# DSP.net
KiCad netlist of a schematic drawn in Altium Designer
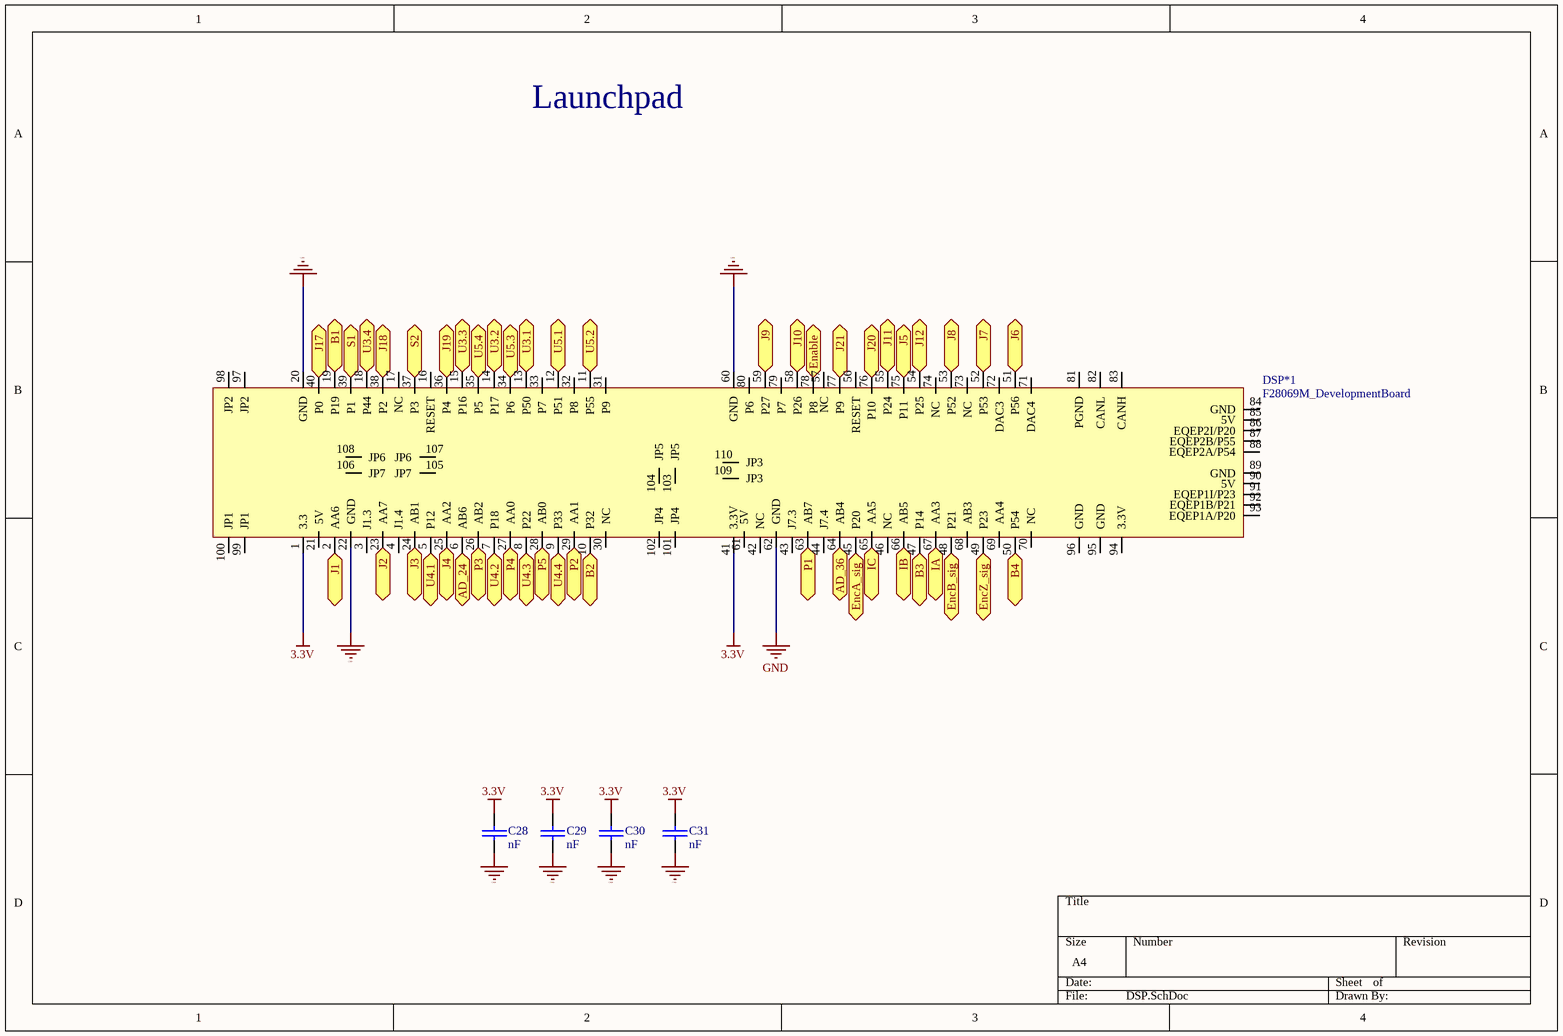
[diagram p0: DSP.SchDoc]

(export (version "E")
  (design (tool "Eeschema 10.0.6"))
  (components
    (comp (ref "C28")
      (value "nF")
      (footprint "1206")
      (description "Condensador")
      (libsource (lib "SCH_Lib") (part "Condensador"))
    )
    (comp (ref "C29")
      (value "nF")
      (footprint "1206")
      (description "Condensador")
      (libsource (lib "SCH_Lib") (part "Condensador"))
    )
    (comp (ref "C30")
      (value "nF")
      (footprint "1206")
      (description "Condensador")
      (libsource (lib "SCH_Lib") (part "Condensador"))
    )
    (comp (ref "C31")
      (value "nF")
      (footprint "1206")
      (description "Condensador")
      (libsource (lib "SCH_Lib") (part "Condensador"))
    )
    (comp (ref "DSP*1")
      (value "F28069M_DevelopmentBoard")
      (footprint "F28069M_DevelopmentBoardDOWN")
      (libsource (lib "DSP") (part "F28069M_DevelopmentBoard"))
    )
  )
  (nets
    (net (code "1") (name "/AD_24") (class "Default")
      (node (ref "DSP*1") (pin "6") (pinfunction "AB6_6") (pintype "passive"))
    )
    (net (code "2") (name "/AD_36") (class "Default")
      (node (ref "DSP*1") (pin "64") (pinfunction "AB4_64") (pintype "passive"))
    )
    (net (code "3") (name "/B1") (class "Default")
      (node (ref "DSP*1") (pin "19") (pinfunction "P19_19") (pintype "passive"))
    )
    (net (code "4") (name "/B2") (class "Default")
      (node (ref "DSP*1") (pin "10") (pinfunction "P32_10") (pintype "passive"))
    )
    (net (code "5") (name "/B3") (class "Default")
      (node (ref "DSP*1") (pin "47") (pinfunction "P14_47") (pintype "passive"))
    )
    (net (code "6") (name "/B4") (class "Default")
      (node (ref "DSP*1") (pin "50") (pinfunction "P54_50") (pintype "passive"))
    )
    (net (code "7") (name "/Enable") (class "Default")
      (node (ref "DSP*1") (pin "78") (pinfunction "P8_78") (pintype "passive"))
    )
    (net (code "8") (name "/EncA_sig") (class "Default")
      (node (ref "DSP*1") (pin "45") (pinfunction "P20_45") (pintype "passive"))
    )
    (net (code "9") (name "/EncB_sig") (class "Default")
      (node (ref "DSP*1") (pin "48") (pinfunction "P21_48") (pintype "passive"))
    )
    (net (code "10") (name "/EncZ_sig") (class "Default")
      (node (ref "DSP*1") (pin "49") (pinfunction "P23_49") (pintype "passive"))
    )
    (net (code "11") (name "/IA") (class "Default")
      (node (ref "DSP*1") (pin "67") (pinfunction "AA3_67") (pintype "passive"))
    )
    (net (code "12") (name "/IB") (class "Default")
      (node (ref "DSP*1") (pin "66") (pinfunction "AB5_66") (pintype "passive"))
    )
    (net (code "13") (name "/IC") (class "Default")
      (node (ref "DSP*1") (pin "65") (pinfunction "AA5_65") (pintype "passive"))
    )
    (net (code "14") (name "/J1") (class "Default")
      (node (ref "DSP*1") (pin "2") (pinfunction "AA6_2") (pintype "passive"))
    )
    (net (code "15") (name "/J2") (class "Default")
      (node (ref "DSP*1") (pin "23") (pinfunction "AA7_23") (pintype "passive"))
    )
    (net (code "16") (name "/J3") (class "Default")
      (node (ref "DSP*1") (pin "24") (pinfunction "AB1_24") (pintype "passive"))
    )
    (net (code "17") (name "/J4") (class "Default")
      (node (ref "DSP*1") (pin "25") (pinfunction "AA2_25") (pintype "passive"))
    )
    (net (code "18") (name "/J5") (class "Default")
      (node (ref "DSP*1") (pin "75") (pinfunction "P11_75") (pintype "passive"))
    )
    (net (code "19") (name "/J6") (class "Default")
      (node (ref "DSP*1") (pin "51") (pinfunction "P56_51") (pintype "passive"))
    )
    (net (code "20") (name "/J7") (class "Default")
      (node (ref "DSP*1") (pin "52") (pinfunction "P53_52") (pintype "passive"))
    )
    (net (code "21") (name "/J8") (class "Default")
      (node (ref "DSP*1") (pin "53") (pinfunction "P52_53") (pintype "passive"))
    )
    (net (code "22") (name "/J9") (class "Default")
      (node (ref "DSP*1") (pin "59") (pinfunction "P27_59") (pintype "passive"))
    )
    (net (code "23") (name "/J10") (class "Default")
      (node (ref "DSP*1") (pin "58") (pinfunction "P26_58") (pintype "passive"))
    )
    (net (code "24") (name "/J11") (class "Default")
      (node (ref "DSP*1") (pin "55") (pinfunction "P24_55") (pintype "passive"))
    )
    (net (code "25") (name "/J12") (class "Default")
      (node (ref "DSP*1") (pin "54") (pinfunction "P25_54") (pintype "passive"))
    )
    (net (code "26") (name "/J17") (class "Default")
      (node (ref "DSP*1") (pin "40") (pinfunction "P0_40") (pintype "passive"))
    )
    (net (code "27") (name "/J18") (class "Default")
      (node (ref "DSP*1") (pin "38") (pinfunction "P2_38") (pintype "passive"))
    )
    (net (code "28") (name "/J19") (class "Default")
      (node (ref "DSP*1") (pin "36") (pinfunction "P4_36") (pintype "passive"))
    )
    (net (code "29") (name "/J20") (class "Default")
      (node (ref "DSP*1") (pin "76") (pinfunction "P10_76") (pintype "passive"))
    )
    (net (code "30") (name "/J21") (class "Default")
      (node (ref "DSP*1") (pin "77") (pinfunction "P9_77") (pintype "passive"))
    )
    (net (code "31") (name "/P1") (class "Default")
      (node (ref "DSP*1") (pin "63") (pinfunction "AB7_63") (pintype "passive"))
    )
    (net (code "32") (name "/P2") (class "Default")
      (node (ref "DSP*1") (pin "29") (pinfunction "AA1_29") (pintype "passive"))
    )
    (net (code "33") (name "/P3") (class "Default")
      (node (ref "DSP*1") (pin "26") (pinfunction "AB2_26") (pintype "passive"))
    )
    (net (code "34") (name "/P4") (class "Default")
      (node (ref "DSP*1") (pin "27") (pinfunction "AA0_27") (pintype "passive"))
    )
    (net (code "35") (name "/P5") (class "Default")
      (node (ref "DSP*1") (pin "28") (pinfunction "AB0_28") (pintype "passive"))
    )
    (net (code "36") (name "/S1") (class "Default")
      (node (ref "DSP*1") (pin "39") (pinfunction "P1_39") (pintype "passive"))
    )
    (net (code "37") (name "/S2") (class "Default")
      (node (ref "DSP*1") (pin "37") (pinfunction "P3_37") (pintype "passive"))
    )
    (net (code "38") (name "/U3.1") (class "Default")
      (node (ref "DSP*1") (pin "13") (pinfunction "P50_13") (pintype "passive"))
    )
    (net (code "39") (name "/U3.2") (class "Default")
      (node (ref "DSP*1") (pin "14") (pinfunction "P17_14") (pintype "passive"))
    )
    (net (code "40") (name "/U3.3") (class "Default")
      (node (ref "DSP*1") (pin "15") (pinfunction "P16_15") (pintype "passive"))
    )
    (net (code "41") (name "/U3.4") (class "Default")
      (node (ref "DSP*1") (pin "18") (pinfunction "P44_18") (pintype "passive"))
    )
    (net (code "42") (name "/U4.1") (class "Default")
      (node (ref "DSP*1") (pin "5") (pinfunction "P12_5") (pintype "passive"))
    )
    (net (code "43") (name "/U4.2") (class "Default")
      (node (ref "DSP*1") (pin "7") (pinfunction "P18_7") (pintype "passive"))
    )
    (net (code "44") (name "/U4.3") (class "Default")
      (node (ref "DSP*1") (pin "8") (pinfunction "P22_8") (pintype "passive"))
    )
    (net (code "45") (name "/U4.4") (class "Default")
      (node (ref "DSP*1") (pin "9") (pinfunction "P33_9") (pintype "passive"))
    )
    (net (code "46") (name "/U5.1") (class "Default")
      (node (ref "DSP*1") (pin "12") (pinfunction "P51_12") (pintype "passive"))
    )
    (net (code "47") (name "/U5.2") (class "Default")
      (node (ref "DSP*1") (pin "11") (pinfunction "P55_11") (pintype "passive"))
    )
    (net (code "48") (name "/U5.3") (class "Default")
      (node (ref "DSP*1") (pin "34") (pinfunction "P6_34") (pintype "passive"))
    )
    (net (code "49") (name "/U5.4") (class "Default")
      (node (ref "DSP*1") (pin "35") (pinfunction "P5_35") (pintype "passive"))
    )
    (net (code "50") (name "3.3V") (class "Default")
      (node (ref "C28") (pin "1") (pintype "passive"))
      (node (ref "C29") (pin "1") (pintype "passive"))
      (node (ref "C30") (pin "1") (pintype "passive"))
      (node (ref "C31") (pin "1") (pintype "passive"))
      (node (ref "DSP*1") (pin "1") (pinfunction "3.3_1") (pintype "passive"))
      (node (ref "DSP*1") (pin "41") (pinfunction "3.3V_41") (pintype "passive"))
    )
    (net (code "51") (name "GND") (class "Default")
      (node (ref "C28") (pin "2") (pintype "passive"))
      (node (ref "C29") (pin "2") (pintype "passive"))
      (node (ref "C30") (pin "2") (pintype "passive"))
      (node (ref "C31") (pin "2") (pintype "passive"))
      (node (ref "DSP*1") (pin "20") (pinfunction "GND_20") (pintype "passive"))
      (node (ref "DSP*1") (pin "22") (pinfunction "GND_22") (pintype "passive"))
      (node (ref "DSP*1") (pin "60") (pinfunction "GND_60") (pintype "passive"))
      (node (ref "DSP*1") (pin "62") (pinfunction "GND_62") (pintype "passive"))
    )
    (net (code "52") (name "unconnected-(DSP*1-3.3V-Pad94)") (class "Default")
      (node (ref "DSP*1") (pin "94") (pinfunction "3.3V_94") (pintype "passive"))
    )
    (net (code "53") (name "unconnected-(DSP*1-5V-Pad21)") (class "Default")
      (node (ref "DSP*1") (pin "21") (pinfunction "5V_21") (pintype "passive"))
    )
    (net (code "54") (name "unconnected-(DSP*1-5V-Pad61)") (class "Default")
      (node (ref "DSP*1") (pin "61") (pinfunction "5V_61") (pintype "passive"))
    )
    (net (code "55") (name "unconnected-(DSP*1-5V-Pad85)") (class "Default")
      (node (ref "DSP*1") (pin "85") (pinfunction "5V_85") (pintype "passive"))
    )
    (net (code "56") (name "unconnected-(DSP*1-5V-Pad90)") (class "Default")
      (node (ref "DSP*1") (pin "90") (pinfunction "5V_90") (pintype "passive"))
    )
    (net (code "57") (name "unconnected-(DSP*1-AA4-Pad69)") (class "Default")
      (node (ref "DSP*1") (pin "69") (pinfunction "AA4_69") (pintype "passive"))
    )
    (net (code "58") (name "unconnected-(DSP*1-AB3-Pad68)") (class "Default")
      (node (ref "DSP*1") (pin "68") (pinfunction "AB3_68") (pintype "passive"))
    )
    (net (code "59") (name "unconnected-(DSP*1-CANH-Pad83)") (class "Default")
      (node (ref "DSP*1") (pin "83") (pinfunction "CANH_83") (pintype "passive"))
    )
    (net (code "60") (name "unconnected-(DSP*1-CANL-Pad82)") (class "Default")
      (node (ref "DSP*1") (pin "82") (pinfunction "CANL_82") (pintype "passive"))
    )
    (net (code "61") (name "unconnected-(DSP*1-DAC3-Pad72)") (class "Default")
      (node (ref "DSP*1") (pin "72") (pinfunction "DAC3_72") (pintype "passive"))
    )
    (net (code "62") (name "unconnected-(DSP*1-DAC4-Pad71)") (class "Default")
      (node (ref "DSP*1") (pin "71") (pinfunction "DAC4_71") (pintype "passive"))
    )
    (net (code "63") (name "unconnected-(DSP*1-EQEP1A{slash}P20-Pad93)") (class "Default")
      (node (ref "DSP*1") (pin "93") (pinfunction "EQEP1A/P20_93") (pintype "passive"))
    )
    (net (code "64") (name "unconnected-(DSP*1-EQEP1B{slash}P21-Pad92)") (class "Default")
      (node (ref "DSP*1") (pin "92") (pinfunction "EQEP1B/P21_92") (pintype "passive"))
    )
    (net (code "65") (name "unconnected-(DSP*1-EQEP1I{slash}P23-Pad91)") (class "Default")
      (node (ref "DSP*1") (pin "91") (pinfunction "EQEP1I/P23_91") (pintype "passive"))
    )
    (net (code "66") (name "unconnected-(DSP*1-EQEP2A{slash}P54-Pad88)") (class "Default")
      (node (ref "DSP*1") (pin "88") (pinfunction "EQEP2A/P54_88") (pintype "passive"))
    )
    (net (code "67") (name "unconnected-(DSP*1-EQEP2B{slash}P55-Pad87)") (class "Default")
      (node (ref "DSP*1") (pin "87") (pinfunction "EQEP2B/P55_87") (pintype "passive"))
    )
    (net (code "68") (name "unconnected-(DSP*1-EQEP2I{slash}P20-Pad86)") (class "Default")
      (node (ref "DSP*1") (pin "86") (pinfunction "EQEP2I/P20_86") (pintype "passive"))
    )
    (net (code "69") (name "unconnected-(DSP*1-GND-Pad84)") (class "Default")
      (node (ref "DSP*1") (pin "84") (pinfunction "GND_84") (pintype "passive"))
    )
    (net (code "70") (name "unconnected-(DSP*1-GND-Pad89)") (class "Default")
      (node (ref "DSP*1") (pin "89") (pinfunction "GND_89") (pintype "passive"))
    )
    (net (code "71") (name "unconnected-(DSP*1-GND-Pad95)") (class "Default")
      (node (ref "DSP*1") (pin "95") (pinfunction "GND_95") (pintype "passive"))
    )
    (net (code "72") (name "unconnected-(DSP*1-GND-Pad96)") (class "Default")
      (node (ref "DSP*1") (pin "96") (pinfunction "GND_96") (pintype "passive"))
    )
    (net (code "73") (name "unconnected-(DSP*1-J1.3-Pad3)") (class "Default")
      (node (ref "DSP*1") (pin "3") (pinfunction "J1.3_3") (pintype "passive"))
    )
    (net (code "74") (name "unconnected-(DSP*1-J1.4-Pad4)") (class "Default")
      (node (ref "DSP*1") (pin "4") (pinfunction "J1.4_4") (pintype "passive"))
    )
    (net (code "75") (name "unconnected-(DSP*1-J7.3-Pad43)") (class "Default")
      (node (ref "DSP*1") (pin "43") (pinfunction "J7.3_43") (pintype "passive"))
    )
    (net (code "76") (name "unconnected-(DSP*1-J7.4-Pad44)") (class "Default")
      (node (ref "DSP*1") (pin "44") (pinfunction "J7.4_44") (pintype "passive"))
    )
    (net (code "77") (name "unconnected-(DSP*1-JP1-Pad99)") (class "Default")
      (node (ref "DSP*1") (pin "99") (pinfunction "JP1_99") (pintype "passive"))
    )
    (net (code "78") (name "unconnected-(DSP*1-JP1-Pad100)") (class "Default")
      (node (ref "DSP*1") (pin "100") (pinfunction "JP1_100") (pintype "passive"))
    )
    (net (code "79") (name "unconnected-(DSP*1-JP2-Pad97)") (class "Default")
      (node (ref "DSP*1") (pin "97") (pinfunction "JP2_97") (pintype "passive"))
    )
    (net (code "80") (name "unconnected-(DSP*1-JP2-Pad98)") (class "Default")
      (node (ref "DSP*1") (pin "98") (pinfunction "JP2_98") (pintype "passive"))
    )
    (net (code "81") (name "unconnected-(DSP*1-JP3-Pad109)") (class "Default")
      (node (ref "DSP*1") (pin "109") (pinfunction "JP3_109") (pintype "passive"))
    )
    (net (code "82") (name "unconnected-(DSP*1-JP3-Pad110)") (class "Default")
      (node (ref "DSP*1") (pin "110") (pinfunction "JP3_110") (pintype "passive"))
    )
    (net (code "83") (name "unconnected-(DSP*1-JP4-Pad101)") (class "Default")
      (node (ref "DSP*1") (pin "101") (pinfunction "JP4_101") (pintype "passive"))
    )
    (net (code "84") (name "unconnected-(DSP*1-JP4-Pad102)") (class "Default")
      (node (ref "DSP*1") (pin "102") (pinfunction "JP4_102") (pintype "passive"))
    )
    (net (code "85") (name "unconnected-(DSP*1-JP5-Pad103)") (class "Default")
      (node (ref "DSP*1") (pin "103") (pinfunction "JP5_103") (pintype "passive"))
    )
    (net (code "86") (name "unconnected-(DSP*1-JP5-Pad104)") (class "Default")
      (node (ref "DSP*1") (pin "104") (pinfunction "JP5_104") (pintype "passive"))
    )
    (net (code "87") (name "unconnected-(DSP*1-JP6-Pad107)") (class "Default")
      (node (ref "DSP*1") (pin "107") (pinfunction "JP6_107") (pintype "passive"))
    )
    (net (code "88") (name "unconnected-(DSP*1-JP6-Pad108)") (class "Default")
      (node (ref "DSP*1") (pin "108") (pinfunction "JP6_108") (pintype "passive"))
    )
    (net (code "89") (name "unconnected-(DSP*1-JP7-Pad105)") (class "Default")
      (node (ref "DSP*1") (pin "105") (pinfunction "JP7_105") (pintype "passive"))
    )
    (net (code "90") (name "unconnected-(DSP*1-JP7-Pad106)") (class "Default")
      (node (ref "DSP*1") (pin "106") (pinfunction "JP7_106") (pintype "passive"))
    )
    (net (code "91") (name "unconnected-(DSP*1-NC-Pad17)") (class "Default")
      (node (ref "DSP*1") (pin "17") (pinfunction "NC_17") (pintype "passive"))
    )
    (net (code "92") (name "unconnected-(DSP*1-NC-Pad30)") (class "Default")
      (node (ref "DSP*1") (pin "30") (pinfunction "NC_30") (pintype "passive"))
    )
    (net (code "93") (name "unconnected-(DSP*1-NC-Pad42)") (class "Default")
      (node (ref "DSP*1") (pin "42") (pinfunction "NC_42") (pintype "passive"))
    )
    (net (code "94") (name "unconnected-(DSP*1-NC-Pad46)") (class "Default")
      (node (ref "DSP*1") (pin "46") (pinfunction "NC_46") (pintype "passive"))
    )
    (net (code "95") (name "unconnected-(DSP*1-NC-Pad57)") (class "Default")
      (node (ref "DSP*1") (pin "57") (pinfunction "NC_57") (pintype "passive"))
    )
    (net (code "96") (name "unconnected-(DSP*1-NC-Pad70)") (class "Default")
      (node (ref "DSP*1") (pin "70") (pinfunction "NC_70") (pintype "passive"))
    )
    (net (code "97") (name "unconnected-(DSP*1-NC-Pad73)") (class "Default")
      (node (ref "DSP*1") (pin "73") (pinfunction "NC_73") (pintype "passive"))
    )
    (net (code "98") (name "unconnected-(DSP*1-NC-Pad74)") (class "Default")
      (node (ref "DSP*1") (pin "74") (pinfunction "NC_74") (pintype "passive"))
    )
    (net (code "99") (name "unconnected-(DSP*1-P6-Pad80)") (class "Default")
      (node (ref "DSP*1") (pin "80") (pinfunction "P6_80") (pintype "passive"))
    )
    (net (code "100") (name "unconnected-(DSP*1-P7-Pad33)") (class "Default")
      (node (ref "DSP*1") (pin "33") (pinfunction "P7_33") (pintype "passive"))
    )
    (net (code "101") (name "unconnected-(DSP*1-P7-Pad79)") (class "Default")
      (node (ref "DSP*1") (pin "79") (pinfunction "P7_79") (pintype "passive"))
    )
    (net (code "102") (name "unconnected-(DSP*1-P8-Pad32)") (class "Default")
      (node (ref "DSP*1") (pin "32") (pinfunction "P8_32") (pintype "passive"))
    )
    (net (code "103") (name "unconnected-(DSP*1-P9-Pad31)") (class "Default")
      (node (ref "DSP*1") (pin "31") (pinfunction "P9_31") (pintype "passive"))
    )
    (net (code "104") (name "unconnected-(DSP*1-PGND-Pad81)") (class "Default")
      (node (ref "DSP*1") (pin "81") (pinfunction "PGND_81") (pintype "passive"))
    )
    (net (code "105") (name "unconnected-(DSP*1-RESET-Pad16)") (class "Default")
      (node (ref "DSP*1") (pin "16") (pinfunction "RESET_16") (pintype "passive"))
    )
    (net (code "106") (name "unconnected-(DSP*1-RESET-Pad56)") (class "Default")
      (node (ref "DSP*1") (pin "56") (pinfunction "RESET_56") (pintype "passive"))
    )
  )
)
